# bike_led.net
KiCad netlist of a schematic drawn in EAGLE
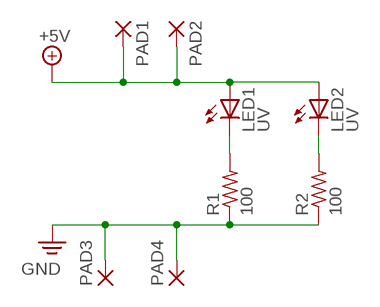
[diagram p0: schematic, sheet 1]

(export (version "E")
  (design (tool "Eeschema 10.0.6"))
  (components
    (comp (ref "LED1")
      (value "UV")
      (footprint "eagle-import:1206")
      (libsource (lib "eagle-import") (part "LEDSMT1206"))
    )
    (comp (ref "LED2")
      (value "UV")
      (footprint "eagle-import:1206")
      (libsource (lib "eagle-import") (part "LEDSMT1206"))
    )
    (comp (ref "PAD1")
      (value "SMD5")
      (footprint "eagle-import:SMD2,54-5,08")
      (libsource (lib "eagle-import") (part "SMD5"))
    )
    (comp (ref "PAD2")
      (value "SMD5")
      (footprint "eagle-import:SMD2,54-5,08")
      (libsource (lib "eagle-import") (part "SMD5"))
    )
    (comp (ref "PAD3")
      (value "SMD5")
      (footprint "eagle-import:SMD2,54-5,08")
      (libsource (lib "eagle-import") (part "SMD5"))
    )
    (comp (ref "PAD4")
      (value "SMD5")
      (footprint "eagle-import:SMD2,54-5,08")
      (libsource (lib "eagle-import") (part "SMD5"))
    )
    (comp (ref "R1")
      (value "100")
      (footprint "eagle-import:R1206")
      (libsource (lib "eagle-import") (part "R-US_R1206"))
    )
    (comp (ref "R2")
      (value "100")
      (footprint "eagle-import:R1206")
      (libsource (lib "eagle-import") (part "R-US_R1206"))
    )
  )
  (nets
    (net (code "1") (name "+5V") (class "Default")
      (node (ref "LED1") (pin "A") (pinfunction "A_A") (pintype "passive"))
      (node (ref "LED2") (pin "A") (pinfunction "A_A") (pintype "passive"))
      (node (ref "PAD1") (pin "1") (pinfunction "P_1") (pintype "passive"))
      (node (ref "PAD2") (pin "1") (pinfunction "P_1") (pintype "passive"))
    )
    (net (code "2") (name "GND") (class "Default")
      (node (ref "PAD3") (pin "1") (pinfunction "P_1") (pintype "passive"))
      (node (ref "PAD4") (pin "1") (pinfunction "P_1") (pintype "passive"))
      (node (ref "R1") (pin "1") (pinfunction "1_1") (pintype "passive"))
      (node (ref "R2") (pin "1") (pinfunction "1_1") (pintype "passive"))
    )
    (net (code "3") (name "Net-(LED1-PadC)") (class "Default")
      (node (ref "LED1") (pin "C") (pinfunction "C_C") (pintype "passive"))
      (node (ref "R1") (pin "2") (pinfunction "2_2") (pintype "passive"))
    )
    (net (code "4") (name "Net-(LED2-PadC)") (class "Default")
      (node (ref "LED2") (pin "C") (pinfunction "C_C") (pintype "passive"))
      (node (ref "R2") (pin "2") (pinfunction "2_2") (pintype "passive"))
    )
  )
)
